# working.net
KiCad netlist of a schematic drawn in EAGLE
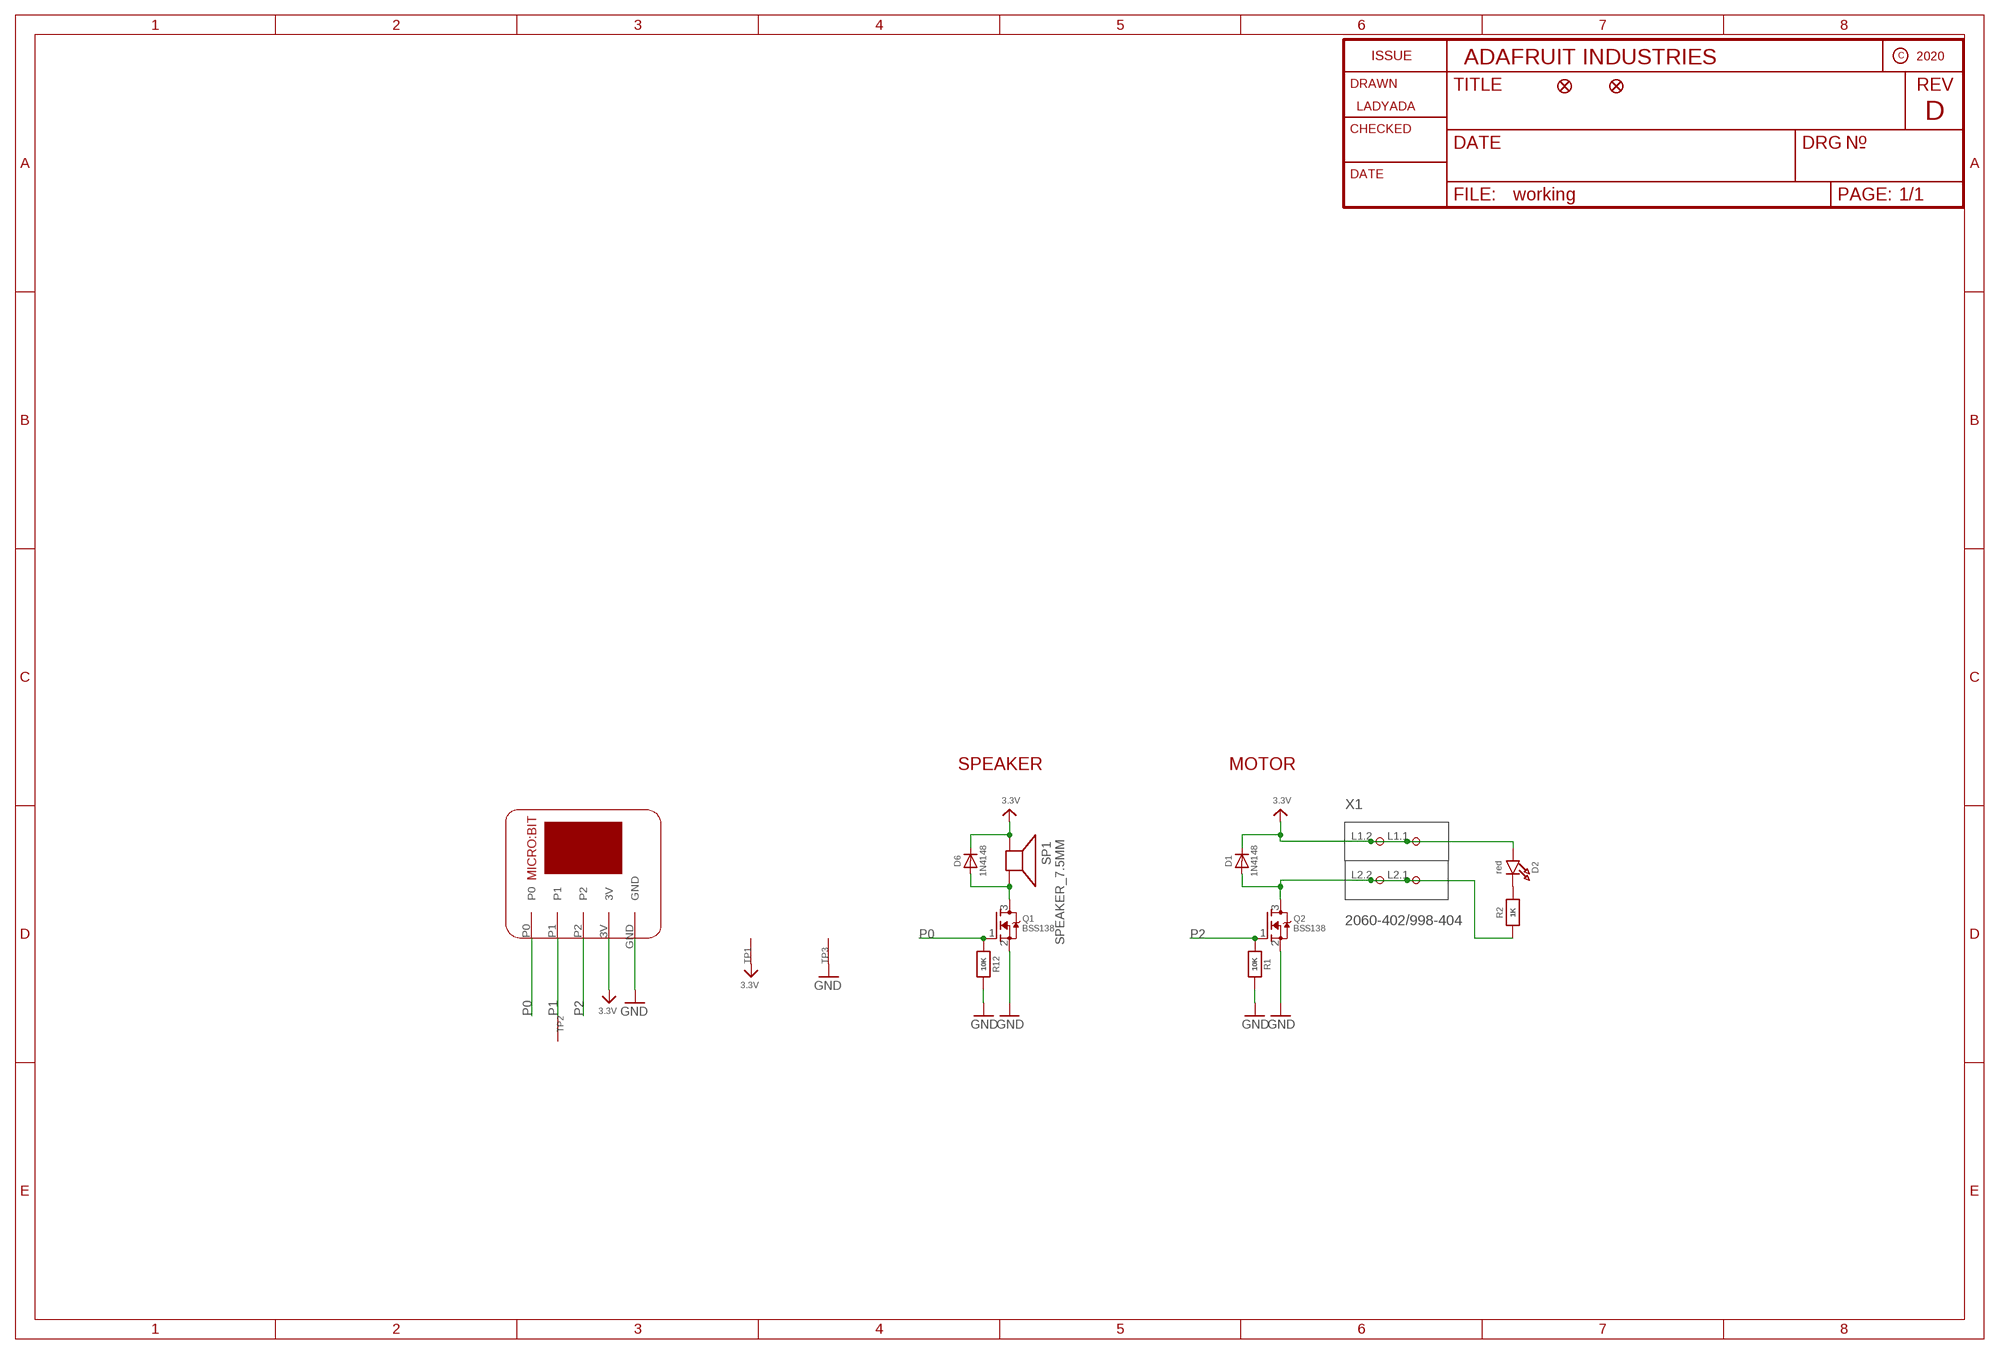
[diagram p0: schematic, sheet 1]

(export (version "E")
  (design (tool "Eeschema 10.0.6"))
  (components
    (comp (ref "D1")
      (value "1N4148")
      (footprint "eagle-import:SOD-323")
      (libsource (lib "eagle-import") (part "DIODESOD-323"))
    )
    (comp (ref "D2")
      (value "red")
      (footprint "eagle-import:CHIPLED_0805_NOOUTLINE")
      (libsource (lib "eagle-import") (part "LED0805_NOOUTLINE"))
    )
    (comp (ref "D6")
      (value "1N4148")
      (footprint "eagle-import:SOD-323")
      (libsource (lib "eagle-import") (part "DIODESOD-323"))
    )
    (comp (ref "FID1")
      (value "FIDUCIAL_1MM")
      (footprint "eagle-import:FIDUCIAL_1MM")
      (libsource (lib "eagle-import") (part "FIDUCIAL_1MM"))
    )
    (comp (ref "FID2")
      (value "FIDUCIAL_1MM")
      (footprint "eagle-import:FIDUCIAL_1MM")
      (libsource (lib "eagle-import") (part "FIDUCIAL_1MM"))
    )
    (comp (ref "MB2")
      (value "MICROBIT_5PIN")
      (footprint "eagle-import:MICROBIT_5SMTNUT")
      (libsource (lib "eagle-import") (part "MICROBIT_5PIN"))
    )
    (comp (ref "Q1")
      (value "BSS138")
      (footprint "eagle-import:SOT23-WIDE")
      (libsource (lib "eagle-import") (part "MOSFET-NWIDE"))
    )
    (comp (ref "Q2")
      (value "BSS138")
      (footprint "eagle-import:SOT23-WIDE")
      (libsource (lib "eagle-import") (part "MOSFET-NWIDE"))
    )
    (comp (ref "R1")
      (value "10K")
      (footprint "eagle-import:0603-NO")
      (libsource (lib "eagle-import") (part "RESISTOR_0603_NOOUT"))
    )
    (comp (ref "R2")
      (value "1K")
      (footprint "eagle-import:0603-NO")
      (libsource (lib "eagle-import") (part "RESISTOR_0603_NOOUT"))
    )
    (comp (ref "R12")
      (value "10K")
      (footprint "eagle-import:0603-NO")
      (libsource (lib "eagle-import") (part "RESISTOR_0603_NOOUT"))
    )
    (comp (ref "SP1")
      (value "SPEAKER_7.5MM")
      (footprint "eagle-import:BUZZER_SMT_7.5MM")
      (libsource (lib "eagle-import") (part "SPEAKER_7.5MM"))
    )
    (comp (ref "TP1")
      (value "SEWTAPPCB_ALLIGATOR")
      (footprint "eagle-import:PCB_ALLI")
      (libsource (lib "eagle-import") (part "SEWTAPPCB_ALLIGATOR"))
    )
    (comp (ref "TP2")
      (value "SEWTAPPCB_ALLIGATOR")
      (footprint "eagle-import:PCB_ALLI")
      (libsource (lib "eagle-import") (part "SEWTAPPCB_ALLIGATOR"))
    )
    (comp (ref "TP3")
      (value "SEWTAPPCB_ALLIGATOR")
      (footprint "eagle-import:PCB_ALLI")
      (libsource (lib "eagle-import") (part "SEWTAPPCB_ALLIGATOR"))
    )
    (comp (ref "X1")
      (value "2060-402/998-404")
      (footprint "eagle-import:P-2060-402_998-404")
      (libsource (lib "eagle-import") (part "2060-402/998-404"))
    )
  )
  (nets
    (net (code "1") (name "/P0") (class "Default")
      (node (ref "MB2") (pin "P0") (pinfunction "P0_P0") (pintype "bidirectional"))
      (node (ref "Q1") (pin "1") (pinfunction "G_1") (pintype "bidirectional"))
      (node (ref "R12") (pin "1") (pinfunction "1_1") (pintype "passive"))
    )
    (net (code "2") (name "/P1") (class "Default")
      (node (ref "MB2") (pin "P1") (pinfunction "P1_P1") (pintype "bidirectional"))
      (node (ref "TP2") (pin "P$1") (pinfunction "SEW_P$1") (pintype "bidirectional"))
    )
    (net (code "3") (name "/P2") (class "Default")
      (node (ref "MB2") (pin "P2") (pinfunction "P2_P2") (pintype "bidirectional"))
      (node (ref "Q2") (pin "1") (pinfunction "G_1") (pintype "bidirectional"))
      (node (ref "R1") (pin "1") (pinfunction "1_1") (pintype "passive"))
    )
    (net (code "4") (name "3.3V") (class "Default")
      (node (ref "D1") (pin "C") (pinfunction "C_C") (pintype "passive"))
      (node (ref "D2") (pin "A") (pinfunction "A_A") (pintype "passive"))
      (node (ref "D6") (pin "C") (pinfunction "C_C") (pintype "passive"))
      (node (ref "MB2") (pin "3V") (pinfunction "3V_3V") (pintype "power_in"))
      (node (ref "SP1") (pin "+") (pinfunction "+_+") (pintype "passive"))
      (node (ref "TP1") (pin "P$1") (pinfunction "SEW_P$1") (pintype "bidirectional"))
      (node (ref "X1") (pin "L1.1") (pinfunction "P1.1_L1.1") (pintype "bidirectional"))
      (node (ref "X1") (pin "L1.2") (pinfunction "P1.2_L1.2") (pintype "bidirectional"))
    )
    (net (code "5") (name "GND") (class "Default")
      (node (ref "MB2") (pin "GND") (pinfunction "GND_GND") (pintype "power_in"))
      (node (ref "Q1") (pin "2") (pinfunction "S_2") (pintype "bidirectional"))
      (node (ref "Q2") (pin "2") (pinfunction "S_2") (pintype "bidirectional"))
      (node (ref "R1") (pin "2") (pinfunction "2_2") (pintype "passive"))
      (node (ref "R12") (pin "2") (pinfunction "2_2") (pintype "passive"))
      (node (ref "TP3") (pin "P$1") (pinfunction "SEW_P$1") (pintype "bidirectional"))
    )
    (net (code "6") (name "Net-(D2-PadC)") (class "Default")
      (node (ref "D2") (pin "C") (pinfunction "C_C") (pintype "passive"))
      (node (ref "R2") (pin "2") (pinfunction "2_2") (pintype "passive"))
    )
    (net (code "7") (name "Net-(Q1-D)") (class "Default")
      (node (ref "D6") (pin "A") (pinfunction "A_A") (pintype "passive"))
      (node (ref "Q1") (pin "3") (pinfunction "D_3") (pintype "bidirectional"))
      (node (ref "SP1") (pin "-") (pinfunction "-_-") (pintype "passive"))
    )
    (net (code "8") (name "Net-(Q2-D)") (class "Default")
      (node (ref "D1") (pin "A") (pinfunction "A_A") (pintype "passive"))
      (node (ref "Q2") (pin "3") (pinfunction "D_3") (pintype "bidirectional"))
      (node (ref "R2") (pin "1") (pinfunction "1_1") (pintype "passive"))
      (node (ref "X1") (pin "L2.1") (pinfunction "P2.1_L2.1") (pintype "bidirectional"))
      (node (ref "X1") (pin "L2.2") (pinfunction "P2.2_L2.2") (pintype "bidirectional"))
    )
  )
)
